# pro_mini_a7105_shield_working.net
KiCad netlist of a schematic drawn in EAGLE
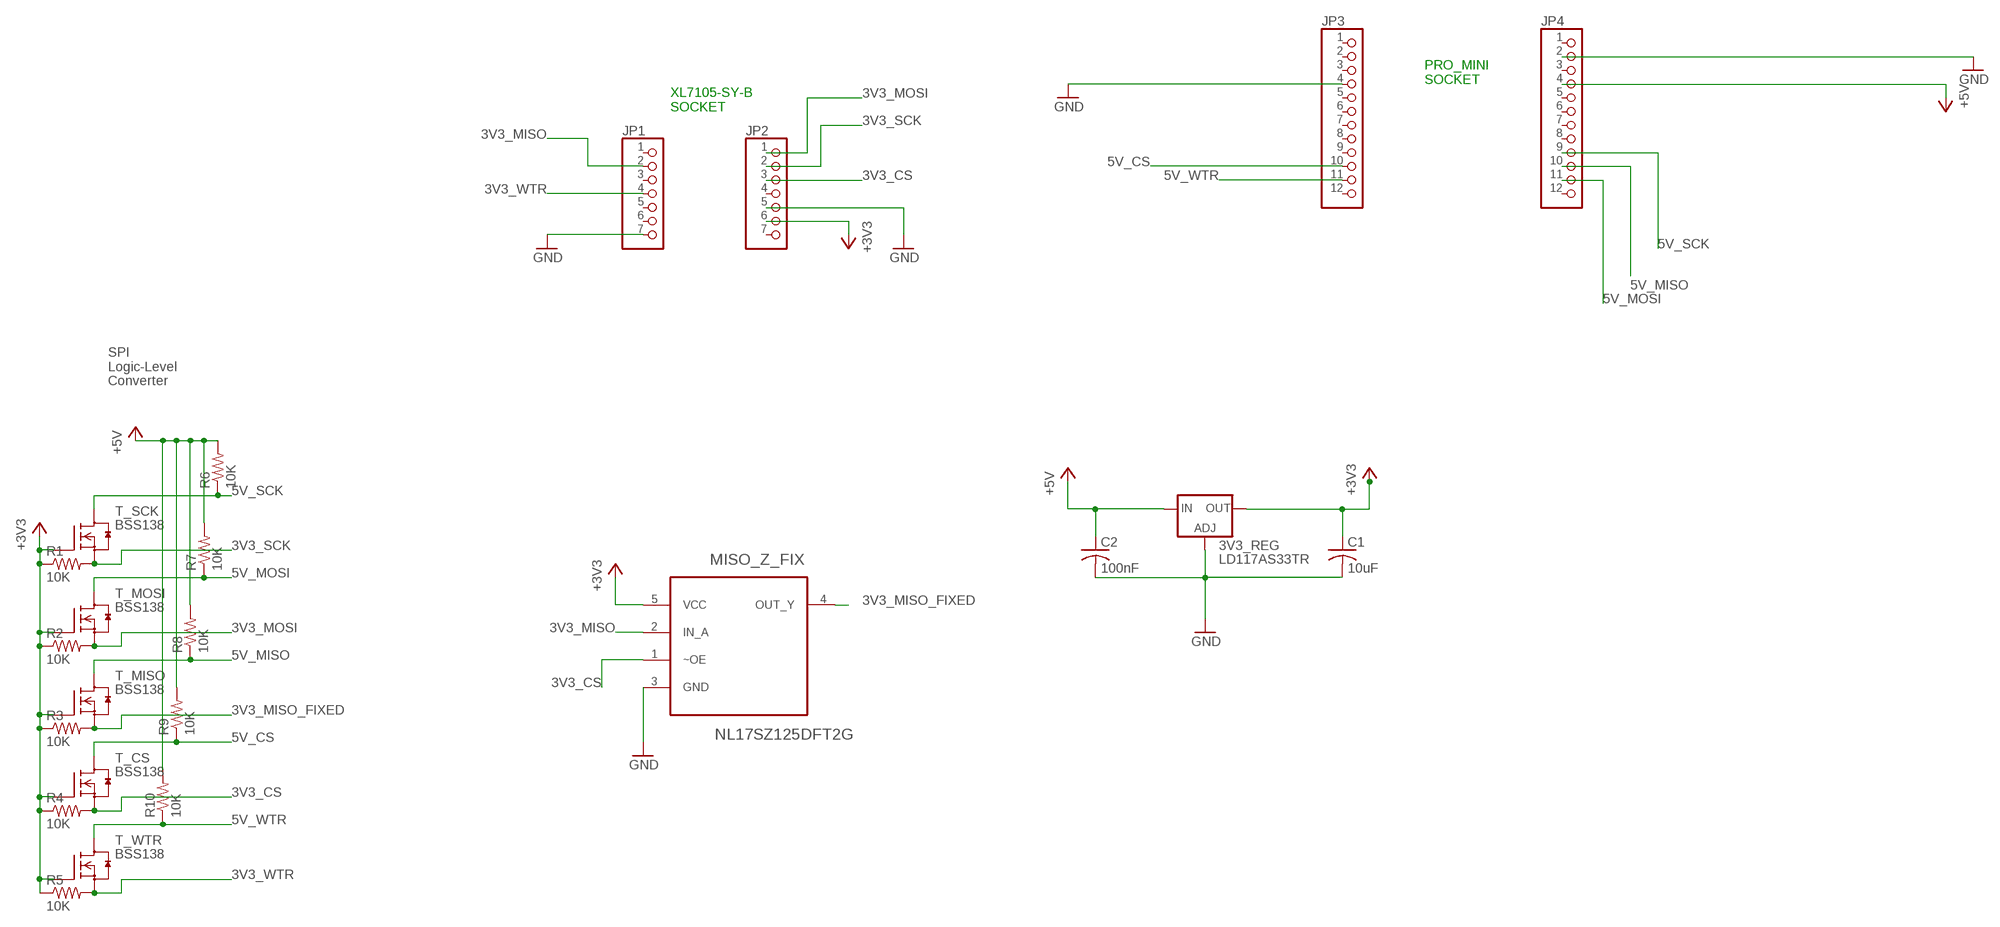
[diagram p0: schematic, sheet 1]

(export (version "E")
  (design (tool "Eeschema 10.0.6"))
  (components
    (comp (ref "3V3_REG")
      (value "LD117AS33TR")
      (footprint "eagle-import:SOT223")
      (libsource (lib "eagle-import") (part "LD117A?S33TR"))
    )
    (comp (ref "C1")
      (value "10uF")
      (footprint "eagle-import:C0805")
      (libsource (lib "eagle-import") (part "C-USC0805"))
    )
    (comp (ref "C2")
      (value "100nF")
      (footprint "eagle-import:C0805")
      (libsource (lib "eagle-import") (part "C-USC0805"))
    )
    (comp (ref "JP1")
      (value "PINHD-1X7M")
      (footprint "eagle-import:1X07M")
      (libsource (lib "eagle-import") (part "PINHD-1X7M"))
    )
    (comp (ref "JP2")
      (value "PINHD-1X7M")
      (footprint "eagle-import:1X07M")
      (libsource (lib "eagle-import") (part "PINHD-1X7M"))
    )
    (comp (ref "JP3")
      (value "PINHD-1X12")
      (footprint "eagle-import:1X12")
      (libsource (lib "eagle-import") (part "PINHD-1X12"))
    )
    (comp (ref "JP4")
      (value "PINHD-1X12")
      (footprint "eagle-import:1X12")
      (libsource (lib "eagle-import") (part "PINHD-1X12"))
    )
    (comp (ref "MISO_Z_FIX")
      (value "NL17SZ125DFT2G")
      (footprint "eagle-import:SOT65P210X110-5N")
      (libsource (lib "eagle-import") (part "NL17SZ125DFT2G"))
    )
    (comp (ref "R1")
      (value "10K")
      (footprint "eagle-import:R0805")
      (libsource (lib "eagle-import") (part "R-US_R0805"))
    )
    (comp (ref "R2")
      (value "10K")
      (footprint "eagle-import:R0805")
      (libsource (lib "eagle-import") (part "R-US_R0805"))
    )
    (comp (ref "R3")
      (value "10K")
      (footprint "eagle-import:R0805")
      (libsource (lib "eagle-import") (part "R-US_R0805"))
    )
    (comp (ref "R4")
      (value "10K")
      (footprint "eagle-import:R0805")
      (libsource (lib "eagle-import") (part "R-US_R0805"))
    )
    (comp (ref "R5")
      (value "10K")
      (footprint "eagle-import:R0805")
      (libsource (lib "eagle-import") (part "R-US_R0805"))
    )
    (comp (ref "R6")
      (value "10K")
      (footprint "eagle-import:R0805")
      (libsource (lib "eagle-import") (part "R-US_R0805"))
    )
    (comp (ref "R7")
      (value "10K")
      (footprint "eagle-import:R0805")
      (libsource (lib "eagle-import") (part "R-US_R0805"))
    )
    (comp (ref "R8")
      (value "10K")
      (footprint "eagle-import:R0805")
      (libsource (lib "eagle-import") (part "R-US_R0805"))
    )
    (comp (ref "R9")
      (value "10K")
      (footprint "eagle-import:R0805")
      (libsource (lib "eagle-import") (part "R-US_R0805"))
    )
    (comp (ref "R10")
      (value "10K")
      (footprint "eagle-import:R0805")
      (libsource (lib "eagle-import") (part "R-US_R0805"))
    )
    (comp (ref "T_CS")
      (value "BSS138")
      (footprint "eagle-import:SOT23")
      (libsource (lib "eagle-import") (part "BSS138"))
    )
    (comp (ref "T_MISO")
      (value "BSS138")
      (footprint "eagle-import:SOT23")
      (libsource (lib "eagle-import") (part "BSS138"))
    )
    (comp (ref "T_MOSI")
      (value "BSS138")
      (footprint "eagle-import:SOT23")
      (libsource (lib "eagle-import") (part "BSS138"))
    )
    (comp (ref "T_SCK")
      (value "BSS138")
      (footprint "eagle-import:SOT23")
      (libsource (lib "eagle-import") (part "BSS138"))
    )
    (comp (ref "T_WTR")
      (value "BSS138")
      (footprint "eagle-import:SOT23")
      (libsource (lib "eagle-import") (part "BSS138"))
    )
  )
  (nets
    (net (code "1") (name "+3V3") (class "Default")
      (node (ref "3V3_REG") (pin "4") (pinfunction "OUT_4") (pintype "passive"))
      (node (ref "C1") (pin "1") (pinfunction "1_1") (pintype "passive"))
      (node (ref "JP2") (pin "6") (pinfunction "6_6") (pintype "passive"))
      (node (ref "MISO_Z_FIX") (pin "5") (pinfunction "VCC_5") (pintype "power_in"))
      (node (ref "R1") (pin "1") (pinfunction "1_1") (pintype "passive"))
      (node (ref "R2") (pin "1") (pinfunction "1_1") (pintype "passive"))
      (node (ref "R3") (pin "1") (pinfunction "1_1") (pintype "passive"))
      (node (ref "R4") (pin "1") (pinfunction "1_1") (pintype "passive"))
      (node (ref "R5") (pin "1") (pinfunction "1_1") (pintype "passive"))
      (node (ref "T_CS") (pin "1") (pinfunction "G_1") (pintype "passive"))
      (node (ref "T_MISO") (pin "1") (pinfunction "G_1") (pintype "passive"))
      (node (ref "T_MOSI") (pin "1") (pinfunction "G_1") (pintype "passive"))
      (node (ref "T_SCK") (pin "1") (pinfunction "G_1") (pintype "passive"))
      (node (ref "T_WTR") (pin "1") (pinfunction "G_1") (pintype "passive"))
    )
    (net (code "2") (name "+5V") (class "Default")
      (node (ref "3V3_REG") (pin "3") (pinfunction "IN_3") (pintype "input"))
      (node (ref "C2") (pin "1") (pinfunction "1_1") (pintype "passive"))
      (node (ref "JP4") (pin "4") (pinfunction "4_4") (pintype "passive"))
      (node (ref "R10") (pin "2") (pinfunction "2_2") (pintype "passive"))
      (node (ref "R6") (pin "2") (pinfunction "2_2") (pintype "passive"))
      (node (ref "R7") (pin "2") (pinfunction "2_2") (pintype "passive"))
      (node (ref "R8") (pin "2") (pinfunction "2_2") (pintype "passive"))
      (node (ref "R9") (pin "2") (pinfunction "2_2") (pintype "passive"))
    )
    (net (code "3") (name "/3V3_CS") (class "Default")
      (node (ref "JP2") (pin "3") (pinfunction "3_3") (pintype "passive"))
      (node (ref "MISO_Z_FIX") (pin "1") (pinfunction "~{OE}_1") (pintype "input"))
      (node (ref "R4") (pin "2") (pinfunction "2_2") (pintype "passive"))
      (node (ref "T_CS") (pin "2") (pinfunction "S_2") (pintype "passive"))
    )
    (net (code "4") (name "/3V3_MISO") (class "Default")
      (node (ref "JP1") (pin "2") (pinfunction "2_2") (pintype "passive"))
      (node (ref "MISO_Z_FIX") (pin "2") (pinfunction "IN_A_2") (pintype "input"))
    )
    (net (code "5") (name "/3V3_MISO_FIXED") (class "Default")
      (node (ref "MISO_Z_FIX") (pin "4") (pinfunction "OUT_Y_4") (pintype "output"))
      (node (ref "R3") (pin "2") (pinfunction "2_2") (pintype "passive"))
      (node (ref "T_MISO") (pin "2") (pinfunction "S_2") (pintype "passive"))
    )
    (net (code "6") (name "/3V3_MOSI") (class "Default")
      (node (ref "JP2") (pin "1") (pinfunction "1_1") (pintype "passive"))
      (node (ref "R2") (pin "2") (pinfunction "2_2") (pintype "passive"))
      (node (ref "T_MOSI") (pin "2") (pinfunction "S_2") (pintype "passive"))
    )
    (net (code "7") (name "/3V3_SCK") (class "Default")
      (node (ref "JP2") (pin "2") (pinfunction "2_2") (pintype "passive"))
      (node (ref "R1") (pin "2") (pinfunction "2_2") (pintype "passive"))
      (node (ref "T_SCK") (pin "2") (pinfunction "S_2") (pintype "passive"))
    )
    (net (code "8") (name "/3V3_WTR") (class "Default")
      (node (ref "JP1") (pin "4") (pinfunction "4_4") (pintype "passive"))
      (node (ref "R5") (pin "2") (pinfunction "2_2") (pintype "passive"))
      (node (ref "T_WTR") (pin "2") (pinfunction "S_2") (pintype "passive"))
    )
    (net (code "9") (name "/5V_CS") (class "Default")
      (node (ref "JP3") (pin "10") (pinfunction "10_10") (pintype "passive"))
      (node (ref "R9") (pin "1") (pinfunction "1_1") (pintype "passive"))
      (node (ref "T_CS") (pin "3") (pinfunction "D_3") (pintype "passive"))
    )
    (net (code "10") (name "/5V_MISO") (class "Default")
      (node (ref "JP4") (pin "10") (pinfunction "10_10") (pintype "passive"))
      (node (ref "R8") (pin "1") (pinfunction "1_1") (pintype "passive"))
      (node (ref "T_MISO") (pin "3") (pinfunction "D_3") (pintype "passive"))
    )
    (net (code "11") (name "/5V_MOSI") (class "Default")
      (node (ref "JP4") (pin "11") (pinfunction "11_11") (pintype "passive"))
      (node (ref "R7") (pin "1") (pinfunction "1_1") (pintype "passive"))
      (node (ref "T_MOSI") (pin "3") (pinfunction "D_3") (pintype "passive"))
    )
    (net (code "12") (name "/5V_SCK") (class "Default")
      (node (ref "JP4") (pin "9") (pinfunction "9_9") (pintype "passive"))
      (node (ref "R6") (pin "1") (pinfunction "1_1") (pintype "passive"))
      (node (ref "T_SCK") (pin "3") (pinfunction "D_3") (pintype "passive"))
    )
    (net (code "13") (name "/5V_WTR") (class "Default")
      (node (ref "JP3") (pin "11") (pinfunction "11_11") (pintype "passive"))
      (node (ref "R10") (pin "1") (pinfunction "1_1") (pintype "passive"))
      (node (ref "T_WTR") (pin "3") (pinfunction "D_3") (pintype "passive"))
    )
    (net (code "14") (name "GND") (class "Default")
      (node (ref "3V3_REG") (pin "1") (pinfunction "ADJ_1") (pintype "input"))
      (node (ref "C1") (pin "2") (pinfunction "2_2") (pintype "passive"))
      (node (ref "C2") (pin "2") (pinfunction "2_2") (pintype "passive"))
      (node (ref "JP1") (pin "7") (pinfunction "7_7") (pintype "passive"))
      (node (ref "JP2") (pin "5") (pinfunction "5_5") (pintype "passive"))
      (node (ref "JP3") (pin "4") (pinfunction "4_4") (pintype "passive"))
      (node (ref "JP4") (pin "2") (pinfunction "2_2") (pintype "passive"))
      (node (ref "MISO_Z_FIX") (pin "3") (pinfunction "GND_3") (pintype "passive"))
    )
    (net (code "15") (name "unconnected-(JP1-Pad1)") (class "Default")
      (node (ref "JP1") (pin "1") (pinfunction "1_1") (pintype "passive"))
    )
    (net (code "16") (name "unconnected-(JP1-Pad3)") (class "Default")
      (node (ref "JP1") (pin "3") (pinfunction "3_3") (pintype "passive"))
    )
    (net (code "17") (name "unconnected-(JP1-Pad5)") (class "Default")
      (node (ref "JP1") (pin "5") (pinfunction "5_5") (pintype "passive"))
    )
    (net (code "18") (name "unconnected-(JP1-Pad6)") (class "Default")
      (node (ref "JP1") (pin "6") (pinfunction "6_6") (pintype "passive"))
    )
    (net (code "19") (name "unconnected-(JP2-Pad4)") (class "Default")
      (node (ref "JP2") (pin "4") (pinfunction "4_4") (pintype "passive"))
    )
    (net (code "20") (name "unconnected-(JP2-Pad7)") (class "Default")
      (node (ref "JP2") (pin "7") (pinfunction "7_7") (pintype "passive"))
    )
    (net (code "21") (name "unconnected-(JP3-Pad1)") (class "Default")
      (node (ref "JP3") (pin "1") (pinfunction "1_1") (pintype "passive"))
    )
    (net (code "22") (name "unconnected-(JP3-Pad2)") (class "Default")
      (node (ref "JP3") (pin "2") (pinfunction "2_2") (pintype "passive"))
    )
    (net (code "23") (name "unconnected-(JP3-Pad3)") (class "Default")
      (node (ref "JP3") (pin "3") (pinfunction "3_3") (pintype "passive"))
    )
    (net (code "24") (name "unconnected-(JP3-Pad5)") (class "Default")
      (node (ref "JP3") (pin "5") (pinfunction "5_5") (pintype "passive"))
    )
    (net (code "25") (name "unconnected-(JP3-Pad6)") (class "Default")
      (node (ref "JP3") (pin "6") (pinfunction "6_6") (pintype "passive"))
    )
    (net (code "26") (name "unconnected-(JP3-Pad7)") (class "Default")
      (node (ref "JP3") (pin "7") (pinfunction "7_7") (pintype "passive"))
    )
    (net (code "27") (name "unconnected-(JP3-Pad8)") (class "Default")
      (node (ref "JP3") (pin "8") (pinfunction "8_8") (pintype "passive"))
    )
    (net (code "28") (name "unconnected-(JP3-Pad9)") (class "Default")
      (node (ref "JP3") (pin "9") (pinfunction "9_9") (pintype "passive"))
    )
    (net (code "29") (name "unconnected-(JP3-Pad12)") (class "Default")
      (node (ref "JP3") (pin "12") (pinfunction "12_12") (pintype "passive"))
    )
    (net (code "30") (name "unconnected-(JP4-Pad1)") (class "Default")
      (node (ref "JP4") (pin "1") (pinfunction "1_1") (pintype "passive"))
    )
    (net (code "31") (name "unconnected-(JP4-Pad3)") (class "Default")
      (node (ref "JP4") (pin "3") (pinfunction "3_3") (pintype "passive"))
    )
    (net (code "32") (name "unconnected-(JP4-Pad5)") (class "Default")
      (node (ref "JP4") (pin "5") (pinfunction "5_5") (pintype "passive"))
    )
    (net (code "33") (name "unconnected-(JP4-Pad6)") (class "Default")
      (node (ref "JP4") (pin "6") (pinfunction "6_6") (pintype "passive"))
    )
    (net (code "34") (name "unconnected-(JP4-Pad7)") (class "Default")
      (node (ref "JP4") (pin "7") (pinfunction "7_7") (pintype "passive"))
    )
    (net (code "35") (name "unconnected-(JP4-Pad8)") (class "Default")
      (node (ref "JP4") (pin "8") (pinfunction "8_8") (pintype "passive"))
    )
    (net (code "36") (name "unconnected-(JP4-Pad12)") (class "Default")
      (node (ref "JP4") (pin "12") (pinfunction "12_12") (pintype "passive"))
    )
  )
)
